# loiterboard.net
KiCad netlist of a schematic drawn in EAGLE
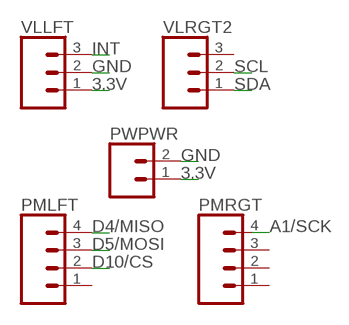
[diagram p0: schematic, sheet 1]

(export (version "E")
  (design (tool "Eeschema 10.0.6"))
  (components
    (comp (ref "PMLFT")
      (value "CONN_04")
      (footprint "eagle-import:1X04")
      (libsource (lib "eagle-import") (part "CONN_04"))
    )
    (comp (ref "PMRGT")
      (value "CONN_04")
      (footprint "eagle-import:1X04")
      (libsource (lib "eagle-import") (part "CONN_04"))
    )
    (comp (ref "PWPWR")
      (value "CONN_02")
      (footprint "eagle-import:1X02")
      (libsource (lib "eagle-import") (part "CONN_02"))
    )
    (comp (ref "VLLFT")
      (value "CONN_03")
      (footprint "eagle-import:1X03")
      (libsource (lib "eagle-import") (part "CONN_03"))
    )
    (comp (ref "VLRGT2")
      (value "CONN_03")
      (footprint "eagle-import:1X03")
      (libsource (lib "eagle-import") (part "CONN_03"))
    )
  )
  (nets
    (net (code "1") (name "/3.3V") (class "Default")
      (node (ref "PWPWR") (pin "1") (pinfunction "1_1") (pintype "passive"))
      (node (ref "VLLFT") (pin "1") (pinfunction "1_1") (pintype "passive"))
    )
    (net (code "2") (name "/A1{slash}SCK") (class "Default")
      (node (ref "PMRGT") (pin "4") (pinfunction "4_4") (pintype "passive"))
    )
    (net (code "3") (name "/D4{slash}MISO") (class "Default")
      (node (ref "PMLFT") (pin "4") (pinfunction "4_4") (pintype "passive"))
    )
    (net (code "4") (name "/D5{slash}MOSI") (class "Default")
      (node (ref "PMLFT") (pin "3") (pinfunction "3_3") (pintype "passive"))
    )
    (net (code "5") (name "/D10{slash}CS") (class "Default")
      (node (ref "PMLFT") (pin "2") (pinfunction "2_2") (pintype "passive"))
    )
    (net (code "6") (name "/GND") (class "Default")
      (node (ref "PWPWR") (pin "2") (pinfunction "2_2") (pintype "passive"))
      (node (ref "VLLFT") (pin "2") (pinfunction "2_2") (pintype "passive"))
    )
    (net (code "7") (name "/INT") (class "Default")
      (node (ref "VLLFT") (pin "3") (pinfunction "3_3") (pintype "passive"))
    )
    (net (code "8") (name "/SCL") (class "Default")
      (node (ref "VLRGT2") (pin "2") (pinfunction "2_2") (pintype "passive"))
    )
    (net (code "9") (name "/SDA") (class "Default")
      (node (ref "VLRGT2") (pin "1") (pinfunction "1_1") (pintype "passive"))
    )
    (net (code "10") (name "unconnected-(PMLFT-Pad1)") (class "Default")
      (node (ref "PMLFT") (pin "1") (pinfunction "1_1") (pintype "passive"))
    )
    (net (code "11") (name "unconnected-(PMRGT-Pad1)") (class "Default")
      (node (ref "PMRGT") (pin "1") (pinfunction "1_1") (pintype "passive"))
    )
    (net (code "12") (name "unconnected-(PMRGT-Pad2)") (class "Default")
      (node (ref "PMRGT") (pin "2") (pinfunction "2_2") (pintype "passive"))
    )
    (net (code "13") (name "unconnected-(PMRGT-Pad3)") (class "Default")
      (node (ref "PMRGT") (pin "3") (pinfunction "3_3") (pintype "passive"))
    )
    (net (code "14") (name "unconnected-(VLRGT2-Pad3)") (class "Default")
      (node (ref "VLRGT2") (pin "3") (pinfunction "3_3") (pintype "passive"))
    )
  )
)
